# 3-PowerPeripherals.net
KiCad netlist of a schematic drawn in Altium Designer
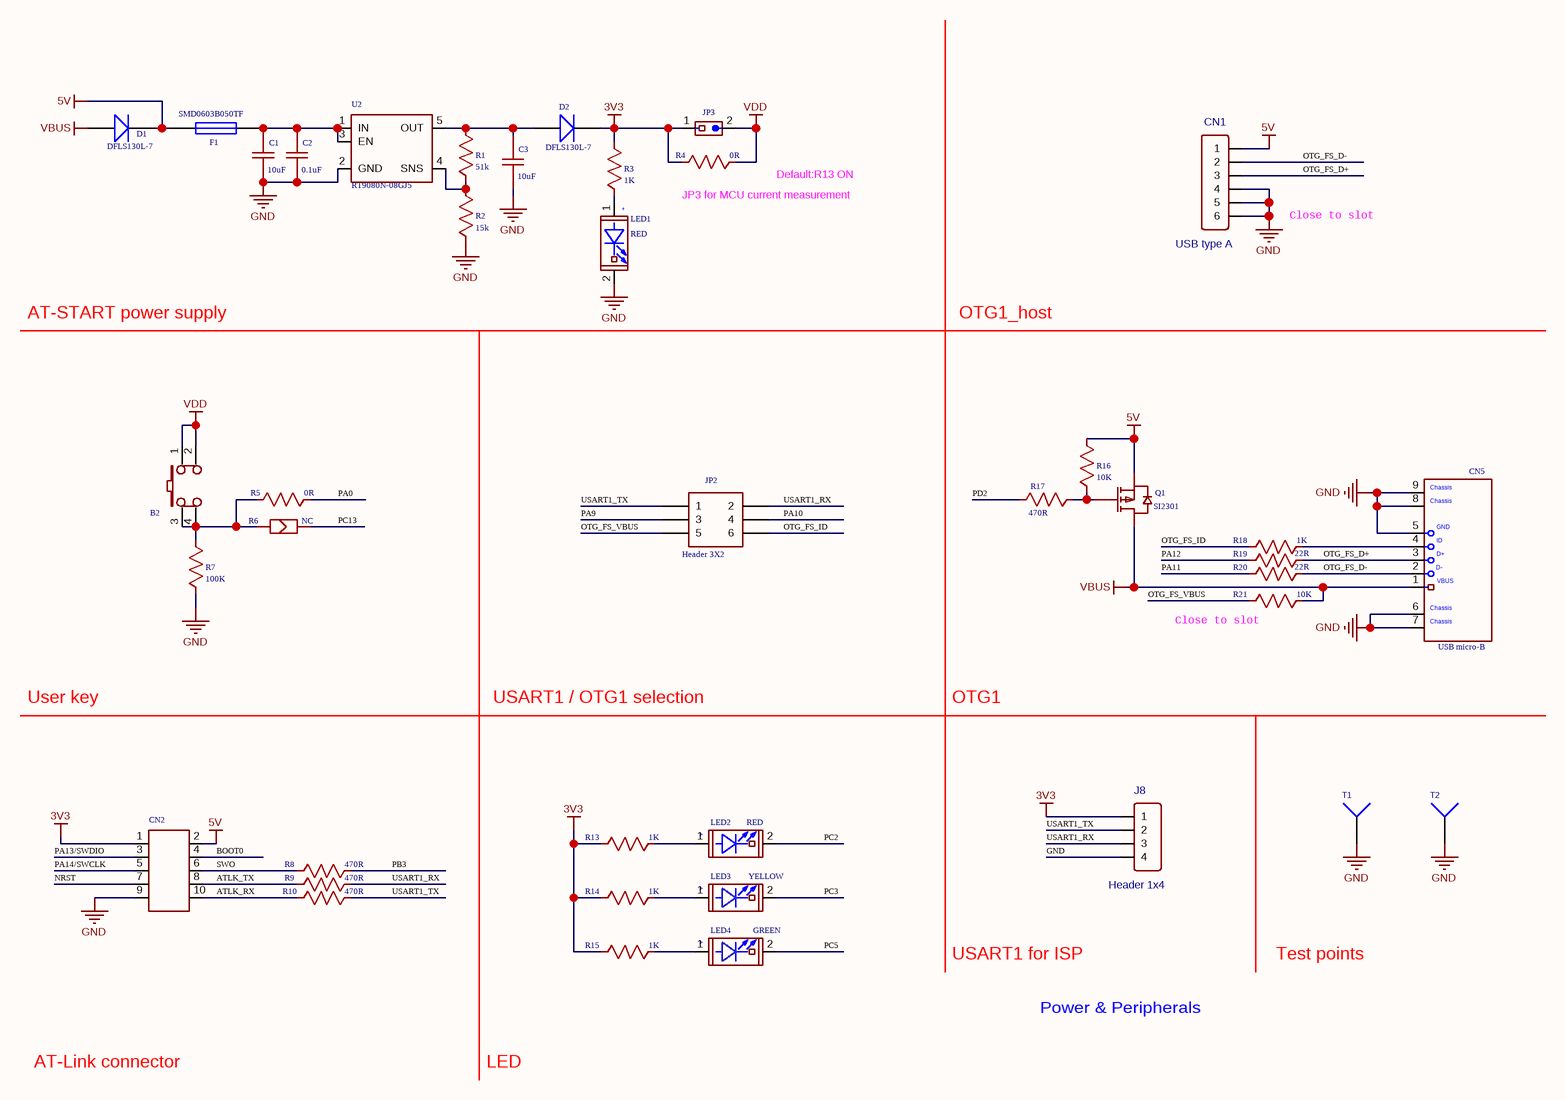
[diagram p0: 3-PowerPeripherals.schdoc]

(export (version "E")
  (design (tool "Eeschema 10.0.6"))
  (components
    (comp (ref "B2")
      (value "BUTTON_SMT,6.0x6.0x4.5mm")
      (fields (field (name "CONTRIBUTOR") "twb17"))
      (libsource (lib "altium-import") (part "root_1_BUTTON_SMT,6.0x6.0x4.5mm_"))
    )
    (comp (ref "C1")
      (value "10uF")
      (fields (field (name "CONTRIBUTOR") "LCEDA_Lib"))
      (libsource (lib "altium-import") (part "root_3_10uF_"))
    )
    (comp (ref "C2")
      (value "0.1uF")
      (fields (field (name "CONTRIBUTOR") "LCEDA_Lib"))
      (libsource (lib "altium-import") (part "root_3_0.1uF_"))
    )
    (comp (ref "C3")
      (value "10uF")
      (fields (field (name "CONTRIBUTOR") "LCEDA_Lib"))
      (libsource (lib "altium-import") (part "root_3_10uF_"))
    )
    (comp (ref "CN1")
      (value "USB type A")
      (fields (field (name "BOM_SUPPLIER PART") "C40877") (field (name "CONTRIBUTOR") "LCEDA_Lib"))
      (libsource (lib "altium-import") (part "root_0_USB type A_"))
    )
    (comp (ref "CN2")
      (value "NC(Header 2x5)")
      (libsource (lib "altium-import") (part "root_0_NC(Header 2x5)_"))
    )
    (comp (ref "CN5") (value "USB micro-B") (libsource (lib "altium-import") (part "root_2_USB micro-B_")))
    (comp (ref "D1")
      (value "DFLS130L-7")
      (fields (field (name "PUBLISHER") "Altium Limited"))
      (libsource (lib "altium-import") (part "root_0_DFLS130L-7_"))
    )
    (comp (ref "D2")
      (value "DFLS130L-7")
      (fields (field (name "PUBLISHER") "Altium Limited"))
      (libsource (lib "altium-import") (part "root_0_DFLS130L-7_"))
    )
    (comp (ref "F1")
      (value "SMD0603B050TF")
      (fields (field (name "PUBLISHER") "Altium Limited"))
      (libsource (lib "altium-import") (part "root_0_SMD0603B050TF_"))
    )
    (comp (ref "J8")
      (value "Header 1x4")
      (fields (field (name "BOM_SUPPLIER PART") "C124378") (field (name "CONTRIBUTOR") "LCEDA_Lib"))
      (libsource (lib "altium-import") (part "root_0_Header 1x4_"))
    )
    (comp (ref "JP2")
      (value "Header 3X2")
      (fields (field (name "PUBLISHER") "Altium Limited") (field (name "CONTRIBUTOR") "twb17"))
      (libsource (lib "altium-import") (part "root_0_Header 3X2_"))
    )
    (comp (ref "JP3")
      (value "NC(Header 1x2)")
      (libsource (lib "altium-import") (part "root_0_NC(Header 1x2)_"))
    )
    (comp (ref "LED1") (value "RED") (libsource (lib "altium-import") (part "root_3_RED_")))
    (comp (ref "LED2") (value "RED") (libsource (lib "altium-import") (part "root_0_RED_")))
    (comp (ref "LED3") (value "YELLOW") (libsource (lib "altium-import") (part "root_0_YELLOW_")))
    (comp (ref "LED4") (value "GREEN") (libsource (lib "altium-import") (part "root_0_GREEN_")))
    (comp (ref "Q1")
      (value "SI2301")
      (fields (field (name "BOM_MANUFACTURER PART") "2301") (field (name "BOM_SUPPLIER PART") "C86773"))
      (libsource (lib "altium-import") (part "root_0_SI2301_"))
    )
    (comp (ref "R1")
      (value "51k")
      (fields (field (name "CONTRIBUTOR") "LCEDA_Lib"))
      (libsource (lib "altium-import") (part "root_1_51k_"))
    )
    (comp (ref "R2")
      (value "15k")
      (fields (field (name "CONTRIBUTOR") "LCEDA_Lib"))
      (libsource (lib "altium-import") (part "root_1_15k_"))
    )
    (comp (ref "R3")
      (value "1K")
      (fields (field (name "CONTRIBUTOR") "LCEDA_Lib"))
      (libsource (lib "altium-import") (part "root_3_1K_"))
    )
    (comp (ref "R4")
      (value "0R")
      (fields (field (name "CONTRIBUTOR") "LCEDA_Lib"))
      (libsource (lib "altium-import") (part "root_2_0R_"))
    )
    (comp (ref "R5")
      (value "0R")
      (fields (field (name "CONTRIBUTOR") "LCEDA_Lib"))
      (libsource (lib "altium-import") (part "root_2_0R_"))
    )
    (comp (ref "R6")
      (value "NC")
      (fields (field (name "CONTRIBUTOR") "twb17"))
      (libsource (lib "altium-import") (part "root_0_NC_"))
    )
    (comp (ref "R7")
      (value "100K")
      (fields (field (name "CONTRIBUTOR") "LCEDA_Lib"))
      (libsource (lib "altium-import") (part "root_3_100K_"))
    )
    (comp (ref "R8")
      (value "470R")
      (fields (field (name "CONTRIBUTOR") "LCEDA_Lib"))
      (libsource (lib "altium-import") (part "root_2_470R_"))
    )
    (comp (ref "R9")
      (value "470R")
      (fields (field (name "CONTRIBUTOR") "LCEDA_Lib"))
      (libsource (lib "altium-import") (part "root_2_470R_"))
    )
    (comp (ref "R10")
      (value "470R")
      (fields (field (name "CONTRIBUTOR") "LCEDA_Lib"))
      (libsource (lib "altium-import") (part "root_2_470R_"))
    )
    (comp (ref "R13")
      (value "1K")
      (fields (field (name "CONTRIBUTOR") "LCEDA_Lib"))
      (libsource (lib "altium-import") (part "root_2_1K_"))
    )
    (comp (ref "R14")
      (value "1K")
      (fields (field (name "CONTRIBUTOR") "LCEDA_Lib"))
      (libsource (lib "altium-import") (part "root_2_1K_"))
    )
    (comp (ref "R15")
      (value "1K")
      (fields (field (name "CONTRIBUTOR") "LCEDA_Lib"))
      (libsource (lib "altium-import") (part "root_2_1K_"))
    )
    (comp (ref "R16")
      (value "10K")
      (fields (field (name "CONTRIBUTOR") "LCEDA_Lib"))
      (libsource (lib "altium-import") (part "root_3_10K_"))
    )
    (comp (ref "R17")
      (value "470R")
      (fields (field (name "CONTRIBUTOR") "LCEDA_Lib"))
      (libsource (lib "altium-import") (part "root_2_470R_"))
    )
    (comp (ref "R18")
      (value "1K")
      (fields (field (name "CONTRIBUTOR") "LCEDA_Lib"))
      (libsource (lib "altium-import") (part "root_2_1K_"))
    )
    (comp (ref "R19")
      (value "22R")
      (fields (field (name "CONTRIBUTOR") "LCEDA_Lib"))
      (libsource (lib "altium-import") (part "root_0_22R_"))
    )
    (comp (ref "R20")
      (value "22R")
      (fields (field (name "CONTRIBUTOR") "LCEDA_Lib"))
      (libsource (lib "altium-import") (part "root_2_22R_"))
    )
    (comp (ref "R21")
      (value "10K")
      (fields (field (name "CONTRIBUTOR") "LCEDA_Lib"))
      (libsource (lib "altium-import") (part "root_2_10K_"))
    )
    (comp (ref "T1")
      (value "Testpoint")
      (fields (field (name "PUBLISHER") "Altium Limited"))
      (libsource (lib "altium-import") (part "root_3_Testpoint_"))
    )
    (comp (ref "T2")
      (value "Testpoint")
      (fields (field (name "PUBLISHER") "Altium Limited"))
      (libsource (lib "altium-import") (part "root_3_Testpoint_"))
    )
    (comp (ref "U2") (value "RT9080N-08GJ5") (libsource (lib "altium-import") (part "root_0_RT9080N-08GJ5_")))
  )
  (nets
    (net (code "1") (name "/ATLK_RX") (class "Default")
      (node (ref "CN2") (pin "10") (pinfunction "10_10") (pintype "passive"))
      (node (ref "R10") (pin "2") (pinfunction "2_2") (pintype "passive"))
    )
    (net (code "2") (name "/ATLK_TX") (class "Default")
      (node (ref "CN2") (pin "8") (pinfunction "8_8") (pintype "passive"))
      (node (ref "R9") (pin "2") (pinfunction "2_2") (pintype "passive"))
    )
    (net (code "3") (name "/BOOT0") (class "Default")
      (node (ref "CN2") (pin "4") (pinfunction "4_4") (pintype "passive"))
    )
    (net (code "4") (name "/NRST") (class "Default")
      (node (ref "CN2") (pin "7") (pinfunction "7_7") (pintype "passive"))
    )
    (net (code "5") (name "/OTG_FS_D+") (class "Default")
      (node (ref "CN1") (pin "3") (pinfunction "3_3") (pintype "passive"))
      (node (ref "CN5") (pin "3") (pinfunction "D+_3") (pintype "passive"))
      (node (ref "R19") (pin "2") (pinfunction "2_2") (pintype "passive"))
    )
    (net (code "6") (name "/OTG_FS_D-") (class "Default")
      (node (ref "CN1") (pin "2") (pinfunction "2_2") (pintype "passive"))
      (node (ref "CN5") (pin "2") (pinfunction "D-_2") (pintype "passive"))
      (node (ref "R20") (pin "1") (pinfunction "1_1") (pintype "passive"))
    )
    (net (code "7") (name "/OTG_FS_ID") (class "Default")
      (node (ref "JP2") (pin "6") (pinfunction "6_6") (pintype "passive"))
      (node (ref "R18") (pin "2") (pinfunction "2_2") (pintype "passive"))
    )
    (net (code "8") (name "/OTG_FS_VBUS") (class "Default")
      (node (ref "JP2") (pin "5") (pinfunction "5_5") (pintype "passive"))
      (node (ref "R21") (pin "2") (pinfunction "2_2") (pintype "passive"))
    )
    (net (code "9") (name "/PA0") (class "Default")
      (node (ref "R5") (pin "1") (pinfunction "1_1") (pintype "passive"))
    )
    (net (code "10") (name "/PA9") (class "Default")
      (node (ref "JP2") (pin "3") (pinfunction "3_3") (pintype "passive"))
    )
    (net (code "11") (name "/PA10") (class "Default")
      (node (ref "JP2") (pin "4") (pinfunction "4_4") (pintype "passive"))
    )
    (net (code "12") (name "/PA11") (class "Default")
      (node (ref "R20") (pin "2") (pinfunction "2_2") (pintype "passive"))
    )
    (net (code "13") (name "/PA12") (class "Default")
      (node (ref "R19") (pin "1") (pinfunction "1_1") (pintype "passive"))
    )
    (net (code "14") (name "/PA13{slash}SWDIO") (class "Default")
      (node (ref "CN2") (pin "3") (pinfunction "3_3") (pintype "passive"))
    )
    (net (code "15") (name "/PA14{slash}SWCLK") (class "Default")
      (node (ref "CN2") (pin "5") (pinfunction "5_5") (pintype "passive"))
    )
    (net (code "16") (name "/PB3") (class "Default")
      (node (ref "R8") (pin "1") (pinfunction "1_1") (pintype "passive"))
    )
    (net (code "17") (name "/PC2") (class "Default")
      (node (ref "LED2") (pin "2") (pinfunction "CATHODE_2") (pintype "passive"))
    )
    (net (code "18") (name "/PC3") (class "Default")
      (node (ref "LED3") (pin "2") (pinfunction "CATHODE_2") (pintype "passive"))
    )
    (net (code "19") (name "/PC5") (class "Default")
      (node (ref "LED4") (pin "2") (pinfunction "CATHODE_2") (pintype "passive"))
    )
    (net (code "20") (name "/PC13") (class "Default")
      (node (ref "R6") (pin "2") (pinfunction "2_2") (pintype "passive"))
    )
    (net (code "21") (name "/PD2") (class "Default")
      (node (ref "R17") (pin "2") (pinfunction "2_2") (pintype "passive"))
    )
    (net (code "22") (name "/SWO") (class "Default")
      (node (ref "CN2") (pin "6") (pinfunction "6_6") (pintype "passive"))
      (node (ref "R8") (pin "2") (pinfunction "2_2") (pintype "passive"))
    )
    (net (code "23") (name "/USART1_RX") (class "Default")
      (node (ref "J8") (pin "3") (pinfunction "3_3") (pintype "passive"))
      (node (ref "JP2") (pin "2") (pinfunction "2_2") (pintype "passive"))
      (node (ref "R9") (pin "1") (pinfunction "1_1") (pintype "passive"))
    )
    (net (code "24") (name "/USART1_TX") (class "Default")
      (node (ref "J8") (pin "2") (pinfunction "2_2") (pintype "passive"))
      (node (ref "JP2") (pin "1") (pinfunction "1_1") (pintype "passive"))
      (node (ref "R10") (pin "1") (pinfunction "1_1") (pintype "passive"))
    )
    (net (code "25") (name "3V3") (class "Default")
      (node (ref "CN2") (pin "1") (pinfunction "1_1") (pintype "passive"))
      (node (ref "D2") (pin "2") (pinfunction "K_2") (pintype "passive"))
      (node (ref "J8") (pin "1") (pinfunction "1_1") (pintype "passive"))
      (node (ref "JP3") (pin "1") (pinfunction "1_1") (pintype "passive"))
      (node (ref "R13") (pin "2") (pinfunction "2_2") (pintype "passive"))
      (node (ref "R14") (pin "2") (pinfunction "2_2") (pintype "passive"))
      (node (ref "R15") (pin "2") (pinfunction "2_2") (pintype "passive"))
      (node (ref "R3") (pin "1") (pinfunction "1_1") (pintype "passive"))
      (node (ref "R4") (pin "2") (pinfunction "2_2") (pintype "passive"))
    )
    (net (code "26") (name "5V") (class "Default")
      (node (ref "CN1") (pin "1") (pinfunction "1_1") (pintype "passive"))
      (node (ref "CN2") (pin "2") (pinfunction "2_2") (pintype "passive"))
      (node (ref "D1") (pin "2") (pinfunction "K_2") (pintype "passive"))
      (node (ref "F1") (pin "1") (pinfunction "1_1") (pintype "passive"))
      (node (ref "Q1") (pin "2") (pinfunction "S_2") (pintype "passive"))
      (node (ref "R16") (pin "1") (pinfunction "1_1") (pintype "passive"))
    )
    (net (code "27") (name "GND") (class "Default")
      (node (ref "C1") (pin "2") (pinfunction "2_2") (pintype "passive"))
      (node (ref "C2") (pin "2") (pinfunction "2_2") (pintype "passive"))
      (node (ref "C3") (pin "2") (pinfunction "2_2") (pintype "passive"))
      (node (ref "CN1") (pin "4") (pinfunction "4_4") (pintype "passive"))
      (node (ref "CN1") (pin "SH1") (pinfunction "5_SH1") (pintype "passive"))
      (node (ref "CN1") (pin "SH2") (pinfunction "6_SH2") (pintype "passive"))
      (node (ref "CN2") (pin "9") (pinfunction "9_9") (pintype "passive"))
      (node (ref "CN5") (pin "5") (pinfunction "GND_5") (pintype "passive"))
      (node (ref "CN5") (pin "6") (pinfunction "6_6") (pintype "passive"))
      (node (ref "CN5") (pin "7") (pinfunction "7_7") (pintype "passive"))
      (node (ref "CN5") (pin "8") (pinfunction "8_8") (pintype "passive"))
      (node (ref "CN5") (pin "9") (pinfunction "9_9") (pintype "passive"))
      (node (ref "J8") (pin "4") (pinfunction "4_4") (pintype "passive"))
      (node (ref "LED1") (pin "2") (pinfunction "CATHODE_2") (pintype "passive"))
      (node (ref "R2") (pin "1") (pinfunction "1_1") (pintype "passive"))
      (node (ref "R7") (pin "2") (pinfunction "2_2") (pintype "passive"))
      (node (ref "T1") (pin "1") (pinfunction "1_1") (pintype "passive"))
      (node (ref "T2") (pin "1") (pinfunction "1_1") (pintype "passive"))
      (node (ref "U2") (pin "2") (pinfunction "GND_2") (pintype "passive"))
    )
    (net (code "28") (name "Net-(B2-Pad3)") (class "Default")
      (node (ref "B2") (pin "3") (pinfunction "3_3") (pintype "passive"))
      (node (ref "B2") (pin "4") (pinfunction "4_4") (pintype "passive"))
      (node (ref "R5") (pin "2") (pinfunction "2_2") (pintype "passive"))
      (node (ref "R6") (pin "1") (pinfunction "1_1") (pintype "passive"))
      (node (ref "R7") (pin "1") (pinfunction "1_1") (pintype "passive"))
    )
    (net (code "29") (name "Net-(CN5-ID)") (class "Default")
      (node (ref "CN5") (pin "4") (pinfunction "ID_4") (pintype "passive"))
      (node (ref "R18") (pin "1") (pinfunction "1_1") (pintype "passive"))
    )
    (net (code "30") (name "Net-(D2-A)") (class "Default")
      (node (ref "C3") (pin "1") (pinfunction "1_1") (pintype "passive"))
      (node (ref "D2") (pin "1") (pinfunction "A_1") (pintype "passive"))
      (node (ref "R1") (pin "2") (pinfunction "2_2") (pintype "passive"))
      (node (ref "U2") (pin "5") (pinfunction "OUT_5") (pintype "passive"))
    )
    (net (code "31") (name "Net-(LED1-ANODE)") (class "Default")
      (node (ref "LED1") (pin "1") (pinfunction "ANODE_1") (pintype "passive"))
      (node (ref "R3") (pin "2") (pinfunction "2_2") (pintype "passive"))
    )
    (net (code "32") (name "Net-(LED2-ANODE)") (class "Default")
      (node (ref "LED2") (pin "1") (pinfunction "ANODE_1") (pintype "passive"))
      (node (ref "R13") (pin "1") (pinfunction "1_1") (pintype "passive"))
    )
    (net (code "33") (name "Net-(LED3-ANODE)") (class "Default")
      (node (ref "LED3") (pin "1") (pinfunction "ANODE_1") (pintype "passive"))
      (node (ref "R14") (pin "1") (pinfunction "1_1") (pintype "passive"))
    )
    (net (code "34") (name "Net-(LED4-ANODE)") (class "Default")
      (node (ref "LED4") (pin "1") (pinfunction "ANODE_1") (pintype "passive"))
      (node (ref "R15") (pin "1") (pinfunction "1_1") (pintype "passive"))
    )
    (net (code "35") (name "Net-(Q1-G)") (class "Default")
      (node (ref "Q1") (pin "1") (pinfunction "G_1") (pintype "passive"))
      (node (ref "R16") (pin "2") (pinfunction "2_2") (pintype "passive"))
      (node (ref "R17") (pin "1") (pinfunction "1_1") (pintype "passive"))
    )
    (net (code "36") (name "Net-(U2-EN)") (class "Default")
      (node (ref "C1") (pin "1") (pinfunction "1_1") (pintype "passive"))
      (node (ref "C2") (pin "1") (pinfunction "1_1") (pintype "passive"))
      (node (ref "F1") (pin "2") (pinfunction "2_2") (pintype "passive"))
      (node (ref "U2") (pin "1") (pinfunction "IN_1") (pintype "passive"))
      (node (ref "U2") (pin "3") (pinfunction "EN_3") (pintype "passive"))
    )
    (net (code "37") (name "Net-(U2-SNS)") (class "Default")
      (node (ref "R1") (pin "1") (pinfunction "1_1") (pintype "passive"))
      (node (ref "R2") (pin "2") (pinfunction "2_2") (pintype "passive"))
      (node (ref "U2") (pin "4") (pinfunction "SNS_4") (pintype "passive"))
    )
    (net (code "38") (name "VBUS") (class "Default")
      (node (ref "CN5") (pin "1") (pinfunction "VBUS_1") (pintype "passive"))
      (node (ref "D1") (pin "1") (pinfunction "A_1") (pintype "passive"))
      (node (ref "Q1") (pin "3") (pinfunction "D_3") (pintype "passive"))
      (node (ref "R21") (pin "1") (pinfunction "1_1") (pintype "passive"))
    )
    (net (code "39") (name "VDD") (class "Default")
      (node (ref "B2") (pin "1") (pinfunction "1_1") (pintype "passive"))
      (node (ref "B2") (pin "2") (pinfunction "2_2") (pintype "passive"))
      (node (ref "JP3") (pin "2") (pinfunction "2_2") (pintype "passive"))
      (node (ref "R4") (pin "1") (pinfunction "1_1") (pintype "passive"))
    )
  )
)
